# PatchPanel.net
KiCad netlist of a schematic drawn in EAGLE
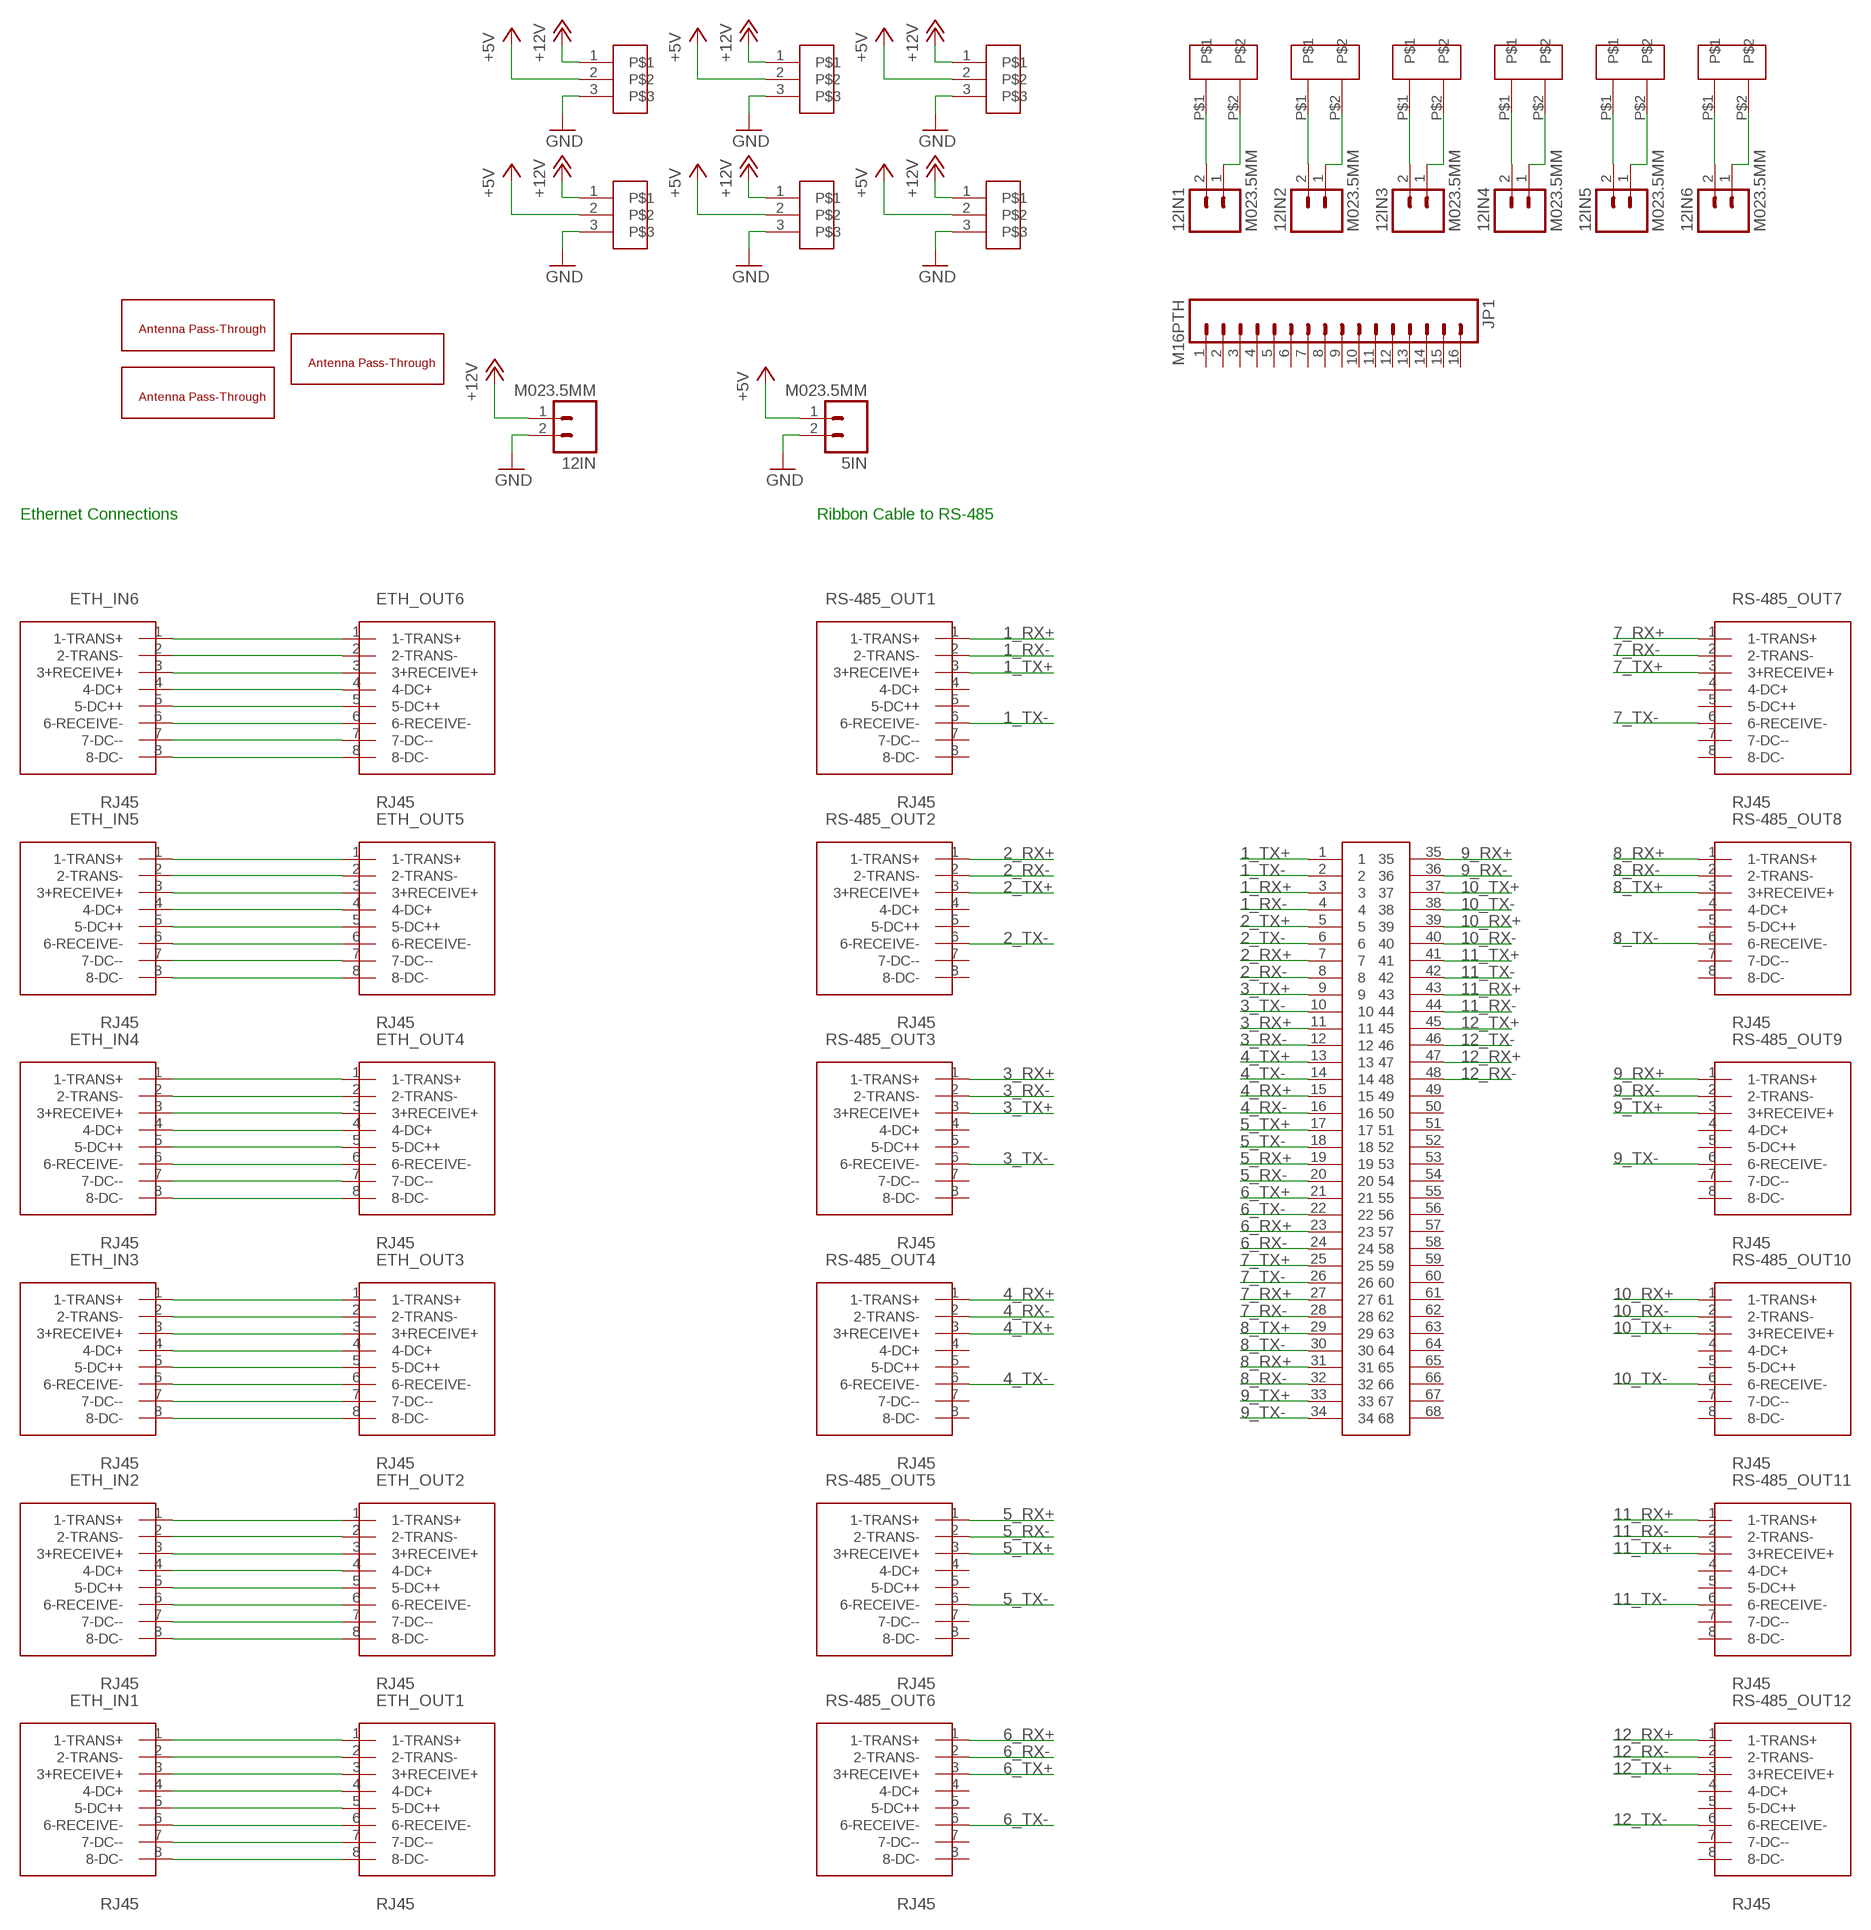
[diagram p0: schematic, sheet 1]

(export (version "E")
  (design (tool "Eeschema 10.0.6"))
  (components
    (comp (ref "5IN")
      (value "M023.5MM")
      (footprint "eagle-import:SCREWTERMINAL-3.5MM-2")
      (libsource (lib "eagle-import") (part "M023.5MM"))
    )
    (comp (ref "12IN")
      (value "M023.5MM")
      (footprint "eagle-import:SCREWTERMINAL-3.5MM-2")
      (libsource (lib "eagle-import") (part "M023.5MM"))
    )
    (comp (ref "12IN1")
      (value "M023.5MM")
      (footprint "eagle-import:SCREWTERMINAL-3.5MM-2")
      (libsource (lib "eagle-import") (part "M023.5MM"))
    )
    (comp (ref "12IN2")
      (value "M023.5MM")
      (footprint "eagle-import:SCREWTERMINAL-3.5MM-2")
      (libsource (lib "eagle-import") (part "M023.5MM"))
    )
    (comp (ref "12IN3")
      (value "M023.5MM")
      (footprint "eagle-import:SCREWTERMINAL-3.5MM-2")
      (libsource (lib "eagle-import") (part "M023.5MM"))
    )
    (comp (ref "12IN4")
      (value "M023.5MM")
      (footprint "eagle-import:SCREWTERMINAL-3.5MM-2")
      (libsource (lib "eagle-import") (part "M023.5MM"))
    )
    (comp (ref "12IN5")
      (value "M023.5MM")
      (footprint "eagle-import:SCREWTERMINAL-3.5MM-2")
      (libsource (lib "eagle-import") (part "M023.5MM"))
    )
    (comp (ref "12IN6")
      (value "M023.5MM")
      (footprint "eagle-import:SCREWTERMINAL-3.5MM-2")
      (libsource (lib "eagle-import") (part "M023.5MM"))
    )
    (comp (ref "ETH_IN1")
      (value "RJ45")
      (footprint "eagle-import:RJ45-CAT5E")
      (libsource (lib "eagle-import") (part "RJ45"))
    )
    (comp (ref "ETH_IN2")
      (value "RJ45")
      (footprint "eagle-import:RJ45-CAT5E")
      (libsource (lib "eagle-import") (part "RJ45"))
    )
    (comp (ref "ETH_IN3")
      (value "RJ45")
      (footprint "eagle-import:RJ45-CAT5E")
      (libsource (lib "eagle-import") (part "RJ45"))
    )
    (comp (ref "ETH_IN4")
      (value "RJ45")
      (footprint "eagle-import:RJ45-CAT5E")
      (libsource (lib "eagle-import") (part "RJ45"))
    )
    (comp (ref "ETH_IN5")
      (value "RJ45")
      (footprint "eagle-import:RJ45-CAT5E")
      (libsource (lib "eagle-import") (part "RJ45"))
    )
    (comp (ref "ETH_IN6")
      (value "RJ45")
      (footprint "eagle-import:RJ45-CAT5E")
      (libsource (lib "eagle-import") (part "RJ45"))
    )
    (comp (ref "ETH_OUT1")
      (value "RJ45")
      (footprint "eagle-import:RJ45-CAT5E")
      (libsource (lib "eagle-import") (part "RJ45"))
    )
    (comp (ref "ETH_OUT2")
      (value "RJ45")
      (footprint "eagle-import:RJ45-CAT5E")
      (libsource (lib "eagle-import") (part "RJ45"))
    )
    (comp (ref "ETH_OUT3")
      (value "RJ45")
      (footprint "eagle-import:RJ45-CAT5E")
      (libsource (lib "eagle-import") (part "RJ45"))
    )
    (comp (ref "ETH_OUT4")
      (value "RJ45")
      (footprint "eagle-import:RJ45-CAT5E")
      (libsource (lib "eagle-import") (part "RJ45"))
    )
    (comp (ref "ETH_OUT5")
      (value "RJ45")
      (footprint "eagle-import:RJ45-CAT5E")
      (libsource (lib "eagle-import") (part "RJ45"))
    )
    (comp (ref "ETH_OUT6")
      (value "RJ45")
      (footprint "eagle-import:RJ45-CAT5E")
      (libsource (lib "eagle-import") (part "RJ45"))
    )
    (comp (ref "JP1")
      (value "M16PTH")
      (footprint "eagle-import:1X16")
      (libsource (lib "eagle-import") (part "M16PTH"))
    )
    (comp (ref "RS-485_OUT1")
      (value "RJ45")
      (footprint "eagle-import:RJ45-CAT5E")
      (libsource (lib "eagle-import") (part "RJ45"))
    )
    (comp (ref "RS-485_OUT2")
      (value "RJ45")
      (footprint "eagle-import:RJ45-CAT5E")
      (libsource (lib "eagle-import") (part "RJ45"))
    )
    (comp (ref "RS-485_OUT3")
      (value "RJ45")
      (footprint "eagle-import:RJ45-CAT5E")
      (libsource (lib "eagle-import") (part "RJ45"))
    )
    (comp (ref "RS-485_OUT4")
      (value "RJ45")
      (footprint "eagle-import:RJ45-CAT5E")
      (libsource (lib "eagle-import") (part "RJ45"))
    )
    (comp (ref "RS-485_OUT5")
      (value "RJ45")
      (footprint "eagle-import:RJ45-CAT5E")
      (libsource (lib "eagle-import") (part "RJ45"))
    )
    (comp (ref "RS-485_OUT6")
      (value "RJ45")
      (footprint "eagle-import:RJ45-CAT5E")
      (libsource (lib "eagle-import") (part "RJ45"))
    )
    (comp (ref "RS-485_OUT7")
      (value "RJ45")
      (footprint "eagle-import:RJ45-CAT5E")
      (libsource (lib "eagle-import") (part "RJ45"))
    )
    (comp (ref "RS-485_OUT8")
      (value "RJ45")
      (footprint "eagle-import:RJ45-CAT5E")
      (libsource (lib "eagle-import") (part "RJ45"))
    )
    (comp (ref "RS-485_OUT9")
      (value "RJ45")
      (footprint "eagle-import:RJ45-CAT5E")
      (libsource (lib "eagle-import") (part "RJ45"))
    )
    (comp (ref "RS-485_OUT10")
      (value "RJ45")
      (footprint "eagle-import:RJ45-CAT5E")
      (libsource (lib "eagle-import") (part "RJ45"))
    )
    (comp (ref "RS-485_OUT11")
      (value "RJ45")
      (footprint "eagle-import:RJ45-CAT5E")
      (libsource (lib "eagle-import") (part "RJ45"))
    )
    (comp (ref "RS-485_OUT12")
      (value "RJ45")
      (footprint "eagle-import:RJ45-CAT5E")
      (libsource (lib "eagle-import") (part "RJ45"))
    )
    (comp (ref "U$1")
      (value "TB60050685100")
      (footprint "eagle-import:60050685100")
      (libsource (lib "eagle-import") (part "TB60050685100"))
    )
    (comp (ref "U$2")
      (value "3PIN")
      (footprint "eagle-import:0.93_")
      (libsource (lib "eagle-import") (part "3PIN"))
    )
    (comp (ref "U$3")
      (value "3PIN")
      (footprint "eagle-import:0.93_")
      (libsource (lib "eagle-import") (part "3PIN"))
    )
    (comp (ref "U$4")
      (value "3PIN")
      (footprint "eagle-import:0.93_")
      (libsource (lib "eagle-import") (part "3PIN"))
    )
    (comp (ref "U$5")
      (value "3PIN")
      (footprint "eagle-import:0.93_")
      (libsource (lib "eagle-import") (part "3PIN"))
    )
    (comp (ref "U$6")
      (value "3PIN")
      (footprint "eagle-import:0.93_")
      (libsource (lib "eagle-import") (part "3PIN"))
    )
    (comp (ref "U$7")
      (value "3PIN")
      (footprint "eagle-import:0.93_")
      (libsource (lib "eagle-import") (part "3PIN"))
    )
    (comp (ref "U$8")
      (value "MLX-2")
      (footprint "eagle-import:42002-2")
      (libsource (lib "eagle-import") (part "MLX-2"))
    )
    (comp (ref "U$9")
      (value "MLX-2")
      (footprint "eagle-import:42002-2")
      (libsource (lib "eagle-import") (part "MLX-2"))
    )
    (comp (ref "U$10")
      (value "MLX-2")
      (footprint "eagle-import:42002-2")
      (libsource (lib "eagle-import") (part "MLX-2"))
    )
    (comp (ref "U$11")
      (value "MLX-2")
      (footprint "eagle-import:42002-2")
      (libsource (lib "eagle-import") (part "MLX-2"))
    )
    (comp (ref "U$12")
      (value "MLX-2")
      (footprint "eagle-import:42002-2")
      (libsource (lib "eagle-import") (part "MLX-2"))
    )
    (comp (ref "U$13")
      (value "MLX-2")
      (footprint "eagle-import:42002-2")
      (libsource (lib "eagle-import") (part "MLX-2"))
    )
    (comp (ref "U$14")
      (value "N-TYPE-THRU")
      (footprint "eagle-import:N-TYPE")
      (libsource (lib "eagle-import") (part "N-TYPE-THRU"))
    )
    (comp (ref "U$15")
      (value "N-TYPE-THRU")
      (footprint "eagle-import:N-TYPE")
      (libsource (lib "eagle-import") (part "N-TYPE-THRU"))
    )
    (comp (ref "U$16")
      (value "SMA-THRU")
      (footprint "eagle-import:SMA")
      (libsource (lib "eagle-import") (part "SMA-THRU"))
    )
  )
  (nets
    (net (code "1") (name "+5V") (class "Default")
      (node (ref "5IN") (pin "1") (pinfunction "1_1") (pintype "passive"))
      (node (ref "U$2") (pin "2") (pinfunction "P$2_2") (pintype "bidirectional"))
      (node (ref "U$3") (pin "2") (pinfunction "P$2_2") (pintype "bidirectional"))
      (node (ref "U$4") (pin "2") (pinfunction "P$2_2") (pintype "bidirectional"))
      (node (ref "U$5") (pin "2") (pinfunction "P$2_2") (pintype "bidirectional"))
      (node (ref "U$6") (pin "2") (pinfunction "P$2_2") (pintype "bidirectional"))
      (node (ref "U$7") (pin "2") (pinfunction "P$2_2") (pintype "bidirectional"))
    )
    (net (code "2") (name "+12V") (class "Default")
      (node (ref "12IN") (pin "1") (pinfunction "1_1") (pintype "passive"))
      (node (ref "U$2") (pin "1") (pinfunction "P$1_1") (pintype "bidirectional"))
      (node (ref "U$3") (pin "1") (pinfunction "P$1_1") (pintype "bidirectional"))
      (node (ref "U$4") (pin "1") (pinfunction "P$1_1") (pintype "bidirectional"))
      (node (ref "U$5") (pin "1") (pinfunction "P$1_1") (pintype "bidirectional"))
      (node (ref "U$6") (pin "1") (pinfunction "P$1_1") (pintype "bidirectional"))
      (node (ref "U$7") (pin "1") (pinfunction "P$1_1") (pintype "bidirectional"))
    )
    (net (code "3") (name "/1_RX+") (class "Default")
      (node (ref "RS-485_OUT1") (pin "1") (pinfunction "1-TRANS+_1") (pintype "bidirectional"))
      (node (ref "U$1") (pin "3") (pinfunction "3_3") (pintype "bidirectional"))
    )
    (net (code "4") (name "/1_RX-") (class "Default")
      (node (ref "RS-485_OUT1") (pin "2") (pinfunction "2-TRANS-_2") (pintype "bidirectional"))
      (node (ref "U$1") (pin "4") (pinfunction "4_4") (pintype "bidirectional"))
    )
    (net (code "5") (name "/1_TX+") (class "Default")
      (node (ref "RS-485_OUT1") (pin "3") (pinfunction "3+RECEIVE+_3") (pintype "bidirectional"))
      (node (ref "U$1") (pin "1") (pinfunction "1_1") (pintype "bidirectional"))
    )
    (net (code "6") (name "/1_TX-") (class "Default")
      (node (ref "RS-485_OUT1") (pin "6") (pinfunction "6-RECEIVE-_6") (pintype "bidirectional"))
      (node (ref "U$1") (pin "2") (pinfunction "2_2") (pintype "bidirectional"))
    )
    (net (code "7") (name "/2_RX+") (class "Default")
      (node (ref "RS-485_OUT2") (pin "1") (pinfunction "1-TRANS+_1") (pintype "bidirectional"))
      (node (ref "U$1") (pin "7") (pinfunction "7_7") (pintype "bidirectional"))
    )
    (net (code "8") (name "/2_RX-") (class "Default")
      (node (ref "RS-485_OUT2") (pin "2") (pinfunction "2-TRANS-_2") (pintype "bidirectional"))
      (node (ref "U$1") (pin "8") (pinfunction "8_8") (pintype "bidirectional"))
    )
    (net (code "9") (name "/2_TX+") (class "Default")
      (node (ref "RS-485_OUT2") (pin "3") (pinfunction "3+RECEIVE+_3") (pintype "bidirectional"))
      (node (ref "U$1") (pin "5") (pinfunction "5_5") (pintype "bidirectional"))
    )
    (net (code "10") (name "/2_TX-") (class "Default")
      (node (ref "RS-485_OUT2") (pin "6") (pinfunction "6-RECEIVE-_6") (pintype "bidirectional"))
      (node (ref "U$1") (pin "6") (pinfunction "6_6") (pintype "bidirectional"))
    )
    (net (code "11") (name "/3_RX+") (class "Default")
      (node (ref "RS-485_OUT3") (pin "1") (pinfunction "1-TRANS+_1") (pintype "bidirectional"))
      (node (ref "U$1") (pin "11") (pinfunction "11_11") (pintype "bidirectional"))
    )
    (net (code "12") (name "/3_RX-") (class "Default")
      (node (ref "RS-485_OUT3") (pin "2") (pinfunction "2-TRANS-_2") (pintype "bidirectional"))
      (node (ref "U$1") (pin "12") (pinfunction "12_12") (pintype "bidirectional"))
    )
    (net (code "13") (name "/3_TX+") (class "Default")
      (node (ref "RS-485_OUT3") (pin "3") (pinfunction "3+RECEIVE+_3") (pintype "bidirectional"))
      (node (ref "U$1") (pin "9") (pinfunction "9_9") (pintype "bidirectional"))
    )
    (net (code "14") (name "/3_TX-") (class "Default")
      (node (ref "RS-485_OUT3") (pin "6") (pinfunction "6-RECEIVE-_6") (pintype "bidirectional"))
      (node (ref "U$1") (pin "10") (pinfunction "10_10") (pintype "bidirectional"))
    )
    (net (code "15") (name "/4_RX+") (class "Default")
      (node (ref "RS-485_OUT4") (pin "1") (pinfunction "1-TRANS+_1") (pintype "bidirectional"))
      (node (ref "U$1") (pin "15") (pinfunction "15_15") (pintype "bidirectional"))
    )
    (net (code "16") (name "/4_RX-") (class "Default")
      (node (ref "RS-485_OUT4") (pin "2") (pinfunction "2-TRANS-_2") (pintype "bidirectional"))
      (node (ref "U$1") (pin "16") (pinfunction "16_16") (pintype "bidirectional"))
    )
    (net (code "17") (name "/4_TX+") (class "Default")
      (node (ref "RS-485_OUT4") (pin "3") (pinfunction "3+RECEIVE+_3") (pintype "bidirectional"))
      (node (ref "U$1") (pin "13") (pinfunction "13_13") (pintype "bidirectional"))
    )
    (net (code "18") (name "/4_TX-") (class "Default")
      (node (ref "RS-485_OUT4") (pin "6") (pinfunction "6-RECEIVE-_6") (pintype "bidirectional"))
      (node (ref "U$1") (pin "14") (pinfunction "14_14") (pintype "bidirectional"))
    )
    (net (code "19") (name "/5_RX+") (class "Default")
      (node (ref "RS-485_OUT5") (pin "1") (pinfunction "1-TRANS+_1") (pintype "bidirectional"))
      (node (ref "U$1") (pin "19") (pinfunction "19_19") (pintype "bidirectional"))
    )
    (net (code "20") (name "/5_RX-") (class "Default")
      (node (ref "RS-485_OUT5") (pin "2") (pinfunction "2-TRANS-_2") (pintype "bidirectional"))
      (node (ref "U$1") (pin "20") (pinfunction "20_20") (pintype "bidirectional"))
    )
    (net (code "21") (name "/5_TX+") (class "Default")
      (node (ref "RS-485_OUT5") (pin "3") (pinfunction "3+RECEIVE+_3") (pintype "bidirectional"))
      (node (ref "U$1") (pin "17") (pinfunction "17_17") (pintype "bidirectional"))
    )
    (net (code "22") (name "/5_TX-") (class "Default")
      (node (ref "RS-485_OUT5") (pin "6") (pinfunction "6-RECEIVE-_6") (pintype "bidirectional"))
      (node (ref "U$1") (pin "18") (pinfunction "18_18") (pintype "bidirectional"))
    )
    (net (code "23") (name "/6_RX+") (class "Default")
      (node (ref "RS-485_OUT6") (pin "1") (pinfunction "1-TRANS+_1") (pintype "bidirectional"))
      (node (ref "U$1") (pin "23") (pinfunction "23_23") (pintype "bidirectional"))
    )
    (net (code "24") (name "/6_RX-") (class "Default")
      (node (ref "RS-485_OUT6") (pin "2") (pinfunction "2-TRANS-_2") (pintype "bidirectional"))
      (node (ref "U$1") (pin "24") (pinfunction "24_24") (pintype "bidirectional"))
    )
    (net (code "25") (name "/6_TX+") (class "Default")
      (node (ref "RS-485_OUT6") (pin "3") (pinfunction "3+RECEIVE+_3") (pintype "bidirectional"))
      (node (ref "U$1") (pin "21") (pinfunction "21_21") (pintype "bidirectional"))
    )
    (net (code "26") (name "/6_TX-") (class "Default")
      (node (ref "RS-485_OUT6") (pin "6") (pinfunction "6-RECEIVE-_6") (pintype "bidirectional"))
      (node (ref "U$1") (pin "22") (pinfunction "22_22") (pintype "bidirectional"))
    )
    (net (code "27") (name "/7_RX+") (class "Default")
      (node (ref "RS-485_OUT7") (pin "1") (pinfunction "1-TRANS+_1") (pintype "bidirectional"))
      (node (ref "U$1") (pin "27") (pinfunction "27_27") (pintype "bidirectional"))
    )
    (net (code "28") (name "/7_RX-") (class "Default")
      (node (ref "RS-485_OUT7") (pin "2") (pinfunction "2-TRANS-_2") (pintype "bidirectional"))
      (node (ref "U$1") (pin "28") (pinfunction "28_28") (pintype "bidirectional"))
    )
    (net (code "29") (name "/7_TX+") (class "Default")
      (node (ref "RS-485_OUT7") (pin "3") (pinfunction "3+RECEIVE+_3") (pintype "bidirectional"))
      (node (ref "U$1") (pin "25") (pinfunction "25_25") (pintype "bidirectional"))
    )
    (net (code "30") (name "/7_TX-") (class "Default")
      (node (ref "RS-485_OUT7") (pin "6") (pinfunction "6-RECEIVE-_6") (pintype "bidirectional"))
      (node (ref "U$1") (pin "26") (pinfunction "26_26") (pintype "bidirectional"))
    )
    (net (code "31") (name "/8_RX+") (class "Default")
      (node (ref "RS-485_OUT8") (pin "1") (pinfunction "1-TRANS+_1") (pintype "bidirectional"))
      (node (ref "U$1") (pin "31") (pinfunction "31_31") (pintype "bidirectional"))
    )
    (net (code "32") (name "/8_RX-") (class "Default")
      (node (ref "RS-485_OUT8") (pin "2") (pinfunction "2-TRANS-_2") (pintype "bidirectional"))
      (node (ref "U$1") (pin "32") (pinfunction "32_32") (pintype "bidirectional"))
    )
    (net (code "33") (name "/8_TX+") (class "Default")
      (node (ref "RS-485_OUT8") (pin "3") (pinfunction "3+RECEIVE+_3") (pintype "bidirectional"))
      (node (ref "U$1") (pin "29") (pinfunction "29_29") (pintype "bidirectional"))
    )
    (net (code "34") (name "/8_TX-") (class "Default")
      (node (ref "RS-485_OUT8") (pin "6") (pinfunction "6-RECEIVE-_6") (pintype "bidirectional"))
      (node (ref "U$1") (pin "30") (pinfunction "30_30") (pintype "bidirectional"))
    )
    (net (code "35") (name "/9_RX+") (class "Default")
      (node (ref "RS-485_OUT9") (pin "1") (pinfunction "1-TRANS+_1") (pintype "bidirectional"))
      (node (ref "U$1") (pin "35") (pinfunction "35_35") (pintype "bidirectional"))
    )
    (net (code "36") (name "/9_RX-") (class "Default")
      (node (ref "RS-485_OUT9") (pin "2") (pinfunction "2-TRANS-_2") (pintype "bidirectional"))
      (node (ref "U$1") (pin "36") (pinfunction "36_36") (pintype "bidirectional"))
    )
    (net (code "37") (name "/9_TX+") (class "Default")
      (node (ref "RS-485_OUT9") (pin "3") (pinfunction "3+RECEIVE+_3") (pintype "bidirectional"))
      (node (ref "U$1") (pin "33") (pinfunction "33_33") (pintype "bidirectional"))
    )
    (net (code "38") (name "/9_TX-") (class "Default")
      (node (ref "RS-485_OUT9") (pin "6") (pinfunction "6-RECEIVE-_6") (pintype "bidirectional"))
      (node (ref "U$1") (pin "34") (pinfunction "34_34") (pintype "bidirectional"))
    )
    (net (code "39") (name "/10_RX+") (class "Default")
      (node (ref "RS-485_OUT10") (pin "1") (pinfunction "1-TRANS+_1") (pintype "bidirectional"))
      (node (ref "U$1") (pin "39") (pinfunction "39_39") (pintype "bidirectional"))
    )
    (net (code "40") (name "/10_RX-") (class "Default")
      (node (ref "RS-485_OUT10") (pin "2") (pinfunction "2-TRANS-_2") (pintype "bidirectional"))
      (node (ref "U$1") (pin "40") (pinfunction "40_40") (pintype "bidirectional"))
    )
    (net (code "41") (name "/10_TX+") (class "Default")
      (node (ref "RS-485_OUT10") (pin "3") (pinfunction "3+RECEIVE+_3") (pintype "bidirectional"))
      (node (ref "U$1") (pin "37") (pinfunction "37_37") (pintype "bidirectional"))
    )
    (net (code "42") (name "/10_TX-") (class "Default")
      (node (ref "RS-485_OUT10") (pin "6") (pinfunction "6-RECEIVE-_6") (pintype "bidirectional"))
      (node (ref "U$1") (pin "38") (pinfunction "38_38") (pintype "bidirectional"))
    )
    (net (code "43") (name "/11_RX+") (class "Default")
      (node (ref "RS-485_OUT11") (pin "1") (pinfunction "1-TRANS+_1") (pintype "bidirectional"))
      (node (ref "U$1") (pin "43") (pinfunction "43_43") (pintype "bidirectional"))
    )
    (net (code "44") (name "/11_RX-") (class "Default")
      (node (ref "RS-485_OUT11") (pin "2") (pinfunction "2-TRANS-_2") (pintype "bidirectional"))
      (node (ref "U$1") (pin "44") (pinfunction "44_44") (pintype "bidirectional"))
    )
    (net (code "45") (name "/11_TX+") (class "Default")
      (node (ref "RS-485_OUT11") (pin "3") (pinfunction "3+RECEIVE+_3") (pintype "bidirectional"))
      (node (ref "U$1") (pin "41") (pinfunction "41_41") (pintype "bidirectional"))
    )
    (net (code "46") (name "/11_TX-") (class "Default")
      (node (ref "RS-485_OUT11") (pin "6") (pinfunction "6-RECEIVE-_6") (pintype "bidirectional"))
      (node (ref "U$1") (pin "42") (pinfunction "42_42") (pintype "bidirectional"))
    )
    (net (code "47") (name "/12_RX+") (class "Default")
      (node (ref "RS-485_OUT12") (pin "1") (pinfunction "1-TRANS+_1") (pintype "bidirectional"))
      (node (ref "U$1") (pin "47") (pinfunction "47_47") (pintype "bidirectional"))
    )
    (net (code "48") (name "/12_RX-") (class "Default")
      (node (ref "RS-485_OUT12") (pin "2") (pinfunction "2-TRANS-_2") (pintype "bidirectional"))
      (node (ref "U$1") (pin "48") (pinfunction "48_48") (pintype "bidirectional"))
    )
    (net (code "49") (name "/12_TX+") (class "Default")
      (node (ref "RS-485_OUT12") (pin "3") (pinfunction "3+RECEIVE+_3") (pintype "bidirectional"))
      (node (ref "U$1") (pin "45") (pinfunction "45_45") (pintype "bidirectional"))
    )
    (net (code "50") (name "/12_TX-") (class "Default")
      (node (ref "RS-485_OUT12") (pin "6") (pinfunction "6-RECEIVE-_6") (pintype "bidirectional"))
      (node (ref "U$1") (pin "46") (pinfunction "46_46") (pintype "bidirectional"))
    )
    (net (code "51") (name "GND") (class "Default")
      (node (ref "12IN") (pin "2") (pinfunction "2_2") (pintype "passive"))
      (node (ref "5IN") (pin "2") (pinfunction "2_2") (pintype "passive"))
      (node (ref "U$2") (pin "3") (pinfunction "P$3_3") (pintype "bidirectional"))
      (node (ref "U$3") (pin "3") (pinfunction "P$3_3") (pintype "bidirectional"))
      (node (ref "U$4") (pin "3") (pinfunction "P$3_3") (pintype "bidirectional"))
      (node (ref "U$5") (pin "3") (pinfunction "P$3_3") (pintype "bidirectional"))
      (node (ref "U$6") (pin "3") (pinfunction "P$3_3") (pintype "bidirectional"))
      (node (ref "U$7") (pin "3") (pinfunction "P$3_3") (pintype "bidirectional"))
    )
    (net (code "52") (name "Net-(12IN1-Pad1)") (class "Default")
      (node (ref "12IN1") (pin "1") (pinfunction "1_1") (pintype "passive"))
      (node (ref "U$8") (pin "P$2") (pinfunction "P$2_P$2") (pintype "bidirectional"))
    )
    (net (code "53") (name "Net-(12IN1-Pad2)") (class "Default")
      (node (ref "12IN1") (pin "2") (pinfunction "2_2") (pintype "passive"))
      (node (ref "U$8") (pin "P$1") (pinfunction "P$1_P$1") (pintype "bidirectional"))
    )
    (net (code "54") (name "Net-(12IN2-Pad1)") (class "Default")
      (node (ref "12IN2") (pin "1") (pinfunction "1_1") (pintype "passive"))
      (node (ref "U$9") (pin "P$2") (pinfunction "P$2_P$2") (pintype "bidirectional"))
    )
    (net (code "55") (name "Net-(12IN2-Pad2)") (class "Default")
      (node (ref "12IN2") (pin "2") (pinfunction "2_2") (pintype "passive"))
      (node (ref "U$9") (pin "P$1") (pinfunction "P$1_P$1") (pintype "bidirectional"))
    )
    (net (code "56") (name "Net-(12IN3-Pad1)") (class "Default")
      (node (ref "12IN3") (pin "1") (pinfunction "1_1") (pintype "passive"))
      (node (ref "U$10") (pin "P$2") (pinfunction "P$2_P$2") (pintype "bidirectional"))
    )
    (net (code "57") (name "Net-(12IN3-Pad2)") (class "Default")
      (node (ref "12IN3") (pin "2") (pinfunction "2_2") (pintype "passive"))
      (node (ref "U$10") (pin "P$1") (pinfunction "P$1_P$1") (pintype "bidirectional"))
    )
    (net (code "58") (name "Net-(12IN4-Pad1)") (class "Default")
      (node (ref "12IN4") (pin "1") (pinfunction "1_1") (pintype "passive"))
      (node (ref "U$11") (pin "P$2") (pinfunction "P$2_P$2") (pintype "bidirectional"))
    )
    (net (code "59") (name "Net-(12IN4-Pad2)") (class "Default")
      (node (ref "12IN4") (pin "2") (pinfunction "2_2") (pintype "passive"))
      (node (ref "U$11") (pin "P$1") (pinfunction "P$1_P$1") (pintype "bidirectional"))
    )
    (net (code "60") (name "Net-(12IN5-Pad1)") (class "Default")
      (node (ref "12IN5") (pin "1") (pinfunction "1_1") (pintype "passive"))
      (node (ref "U$12") (pin "P$2") (pinfunction "P$2_P$2") (pintype "bidirectional"))
    )
    (net (code "61") (name "Net-(12IN5-Pad2)") (class "Default")
      (node (ref "12IN5") (pin "2") (pinfunction "2_2") (pintype "passive"))
      (node (ref "U$12") (pin "P$1") (pinfunction "P$1_P$1") (pintype "bidirectional"))
    )
    (net (code "62") (name "Net-(12IN6-Pad1)") (class "Default")
      (node (ref "12IN6") (pin "1") (pinfunction "1_1") (pintype "passive"))
      (node (ref "U$13") (pin "P$2") (pinfunction "P$2_P$2") (pintype "bidirectional"))
    )
    (net (code "63") (name "Net-(12IN6-Pad2)") (class "Default")
      (node (ref "12IN6") (pin "2") (pinfunction "2_2") (pintype "passive"))
      (node (ref "U$13") (pin "P$1") (pinfunction "P$1_P$1") (pintype "bidirectional"))
    )
    (net (code "64") (name "Net-(ETH_IN1-1-TRANS+)") (class "Default")
      (node (ref "ETH_IN1") (pin "1") (pinfunction "1-TRANS+_1") (pintype "bidirectional"))
      (node (ref "ETH_OUT1") (pin "1") (pinfunction "1-TRANS+_1") (pintype "bidirectional"))
    )
    (net (code "65") (name "Net-(ETH_IN1-2-TRANS-)") (class "Default")
      (node (ref "ETH_IN1") (pin "2") (pinfunction "2-TRANS-_2") (pintype "bidirectional"))
      (node (ref "ETH_OUT1") (pin "2") (pinfunction "2-TRANS-_2") (pintype "bidirectional"))
    )
    (net (code "66") (name "Net-(ETH_IN1-3+RECEIVE+)") (class "Default")
      (node (ref "ETH_IN1") (pin "3") (pinfunction "3+RECEIVE+_3") (pintype "bidirectional"))
      (node (ref "ETH_OUT1") (pin "3") (pinfunction "3+RECEIVE+_3") (pintype "bidirectional"))
    )
    (net (code "67") (name "Net-(ETH_IN1-4-DC+)") (class "Default")
      (node (ref "ETH_IN1") (pin "4") (pinfunction "4-DC+_4") (pintype "bidirectional"))
      (node (ref "ETH_OUT1") (pin "4") (pinfunction "4-DC+_4") (pintype "bidirectional"))
    )
    (net (code "68") (name "Net-(ETH_IN1-5-DC++)") (class "Default")
      (node (ref "ETH_IN1") (pin "5") (pinfunction "5-DC++_5") (pintype "bidirectional"))
      (node (ref "ETH_OUT1") (pin "5") (pinfunction "5-DC++_5") (pintype "bidirectional"))
    )
    (net (code "69") (name "Net-(ETH_IN1-6-RECEIVE-)") (class "Default")
      (node (ref "ETH_IN1") (pin "6") (pinfunction "6-RECEIVE-_6") (pintype "bidirectional"))
      (node (ref "ETH_OUT1") (pin "6") (pinfunction "6-RECEIVE-_6") (pintype "bidirectional"))
    )
    (net (code "70") (name "Net-(ETH_IN1-7-DC--)") (class "Default")
      (node (ref "ETH_IN1") (pin "7") (pinfunction "7-DC--_7") (pintype "bidirectional"))
      (node (ref "ETH_OUT1") (pin "7") (pinfunction "7-DC--_7") (pintype "bidirectional"))
    )
    (net (code "71") (name "Net-(ETH_IN1-8-DC-)") (class "Default")
      (node (ref "ETH_IN1") (pin "8") (pinfunction "8-DC-_8") (pintype "bidirectional"))
      (node (ref "ETH_OUT1") (pin "8") (pinfunction "8-DC-_8") (pintype "bidirectional"))
    )
    (net (code "72") (name "Net-(ETH_IN2-1-TRANS+)") (class "Default")
      (node (ref "ETH_IN2") (pin "1") (pinfunction "1-TRANS+_1") (pintype "bidirectional"))
      (node (ref "ETH_OUT2") (pin "1") (pinfunction "1-TRANS+_1") (pintype "bidirectional"))
    )
    (net (code "73") (name "Net-(ETH_IN2-2-TRANS-)") (class "Default")
      (node (ref "ETH_IN2") (pin "2") (pinfunction "2-TRANS-_2") (pintype "bidirectional"))
      (node (ref "ETH_OUT2") (pin "2") (pinfunction "2-TRANS-_2") (pintype "bidirectional"))
    )
    (net (code "74") (name "Net-(ETH_IN2-3+RECEIVE+)") (class "Default")
      (node (ref "ETH_IN2") (pin "3") (pinfunction "3+RECEIVE+_3") (pintype "bidirectional"))
      (node (ref "ETH_OUT2") (pin "3") (pinfunction "3+RECEIVE+_3") (pintype "bidirectional"))
    )
    (net (code "75") (name "Net-(ETH_IN2-4-DC+)") (class "Default")
      (node (ref "ETH_IN2") (pin "4") (pinfunction "4-DC+_4") (pintype "bidirectional"))
      (node (ref "ETH_OUT2") (pin "4") (pinfunction "4-DC+_4") (pintype "bidirectional"))
    )
    (net (code "76") (name "Net-(ETH_IN2-5-DC++)") (class "Default")
      (node (ref "ETH_IN2") (pin "5") (pinfunction "5-DC++_5") (pintype "bidirectional"))
      (node (ref "ETH_OUT2") (pin "5") (pinfunction "5-DC++_5") (pintype "bidirectional"))
    )
    (net (code "77") (name "Net-(ETH_IN2-6-RECEIVE-)") (class "Default")
      (node (ref "ETH_IN2") (pin "6") (pinfunction "6-RECEIVE-_6") (pintype "bidirectional"))
      (node (ref "ETH_OUT2") (pin "6") (pinfunction "6-RECEIVE-_6") (pintype "bidirectional"))
    )
    (net (code "78") (name "Net-(ETH_IN2-7-DC--)") (class "Default")
      (node (ref "ETH_IN2") (pin "7") (pinfunction "7-DC--_7") (pintype "bidirectional"))
      (node (ref "ETH_OUT2") (pin "7") (pinfunction "7-DC--_7") (pintype "bidirectional"))
    )
    (net (code "79") (name "Net-(ETH_IN2-8-DC-)") (class "Default")
      (node (ref "ETH_IN2") (pin "8") (pinfunction "8-DC-_8") (pintype "bidirectional"))
      (node (ref "ETH_OUT2") (pin "8") (pinfunction "8-DC-_8") (pintype "bidirectional"))
    )
    (net (code "80") (name "Net-(ETH_IN3-1-TRANS+)") (class "Default")
      (node (ref "ETH_IN3") (pin "1") (pinfunction "1-TRANS+_1") (pintype "bidirectional"))
      (node (ref "ETH_OUT3") (pin "1") (pinfunction "1-TRANS+_1") (pintype "bidirectional"))
    )
    (net (code "81") (name "Net-(ETH_IN3-2-TRANS-)") (class "Default")
      (node (ref "ETH_IN3") (pin "2") (pinfunction "2-TRANS-_2") (pintype "bidirectional"))
      (node (ref "ETH_OUT3") (pin "2") (pinfunction "2-TRANS-_2") (pintype "bidirectional"))
    )
    (net (code "82") (name "Net-(ETH_IN3-3+RECEIVE+)") (class "Default")
      (node (ref "ETH_IN3") (pin "3") (pinfunction "3+RECEIVE+_3") (pintype "bidirectional"))
      (node (ref "ETH_OUT3") (pin "3") (pinfunction "3+RECEIVE+_3") (pintype "bidirectional"))
    )
    (net (code "83") (name "Net-(ETH_IN3-4-DC+)") (class "Default")
      (node (ref "ETH_IN3") (pin "4") (pinfunction "4-DC+_4") (pintype "bidirectional"))
      (node (ref "ETH_OUT3") (pin "4") (pinfunction "4-DC+_4") (pintype "bidirectional"))
    )
    (net (code "84") (name "Net-(ETH_IN3-5-DC++)") (class "Default")
      (node (ref "ETH_IN3") (pin "5") (pinfunction "5-DC++_5") (pintype "bidirectional"))
      (node (ref "ETH_OUT3") (pin "5") (pinfunction "5-DC++_5") (pintype "bidirectional"))
    )
    (net (code "85") (name "Net-(ETH_IN3-6-RECEIVE-)") (class "Default")
      (node (ref "ETH_IN3") (pin "6") (pinfunction "6-RECEIVE-_6") (pintype "bidirectional"))
      (node (ref "ETH_OUT3") (pin "6") (pinfunction "6-RECEIVE-_6") (pintype "bidirectional"))
    )
    (net (code "86") (name "Net-(ETH_IN3-7-DC--)") (class "Default")
      (node (ref "ETH_IN3") (pin "7") (pinfunction "7-DC--_7") (pintype "bidirectional"))
      (node (ref "ETH_OUT3") (pin "7") (pinfunction "7-DC--_7") (pintype "bidirectional"))
    )
    (net (code "87") (name "Net-(ETH_IN3-8-DC-)") (class "Default")
      (node (ref "ETH_IN3") (pin "8") (pinfunction "8-DC-_8") (pintype "bidirectional"))
      (node (ref "ETH_OUT3") (pin "8") (pinfunction "8-DC-_8") (pintype "bidirectional"))
    )
    (net (code "88") (name "Net-(ETH_IN4-1-TRANS+)") (class "Default")
      (node (ref "ETH_IN4") (pin "1") (pinfunction "1-TRANS+_1") (pintype "bidirectional"))
      (node (ref "ETH_OUT4") (pin "1") (pinfunction "1-TRANS+_1") (pintype "bidirectional"))
    )
    (net (code "89") (name "Net-(ETH_IN4-2-TRANS-)") (class "Default")
      (node (ref "ETH_IN4") (pin "2") (pinfunction "2-TRANS-_2") (pintype "bidirectional"))
      (node (ref "ETH_OUT4") (pin "2") (pinfunction "2-TRANS-_2") (pintype "bidirectional"))
    )
    (net (code "90") (name "Net-(ETH_IN4-3+RECEIVE+)") (class "Default")
      (node (ref "ETH_IN4") (pin "3") (pinfunction "3+RECEIVE+_3") (pintype "bidirectional"))
      (node (ref "ETH_OUT4") (pin "3") (pinfunction "3+RECEIVE+_3") (pintype "bidirectional"))
    )
    (net (code "91") (name "Net-(ETH_IN4-4-DC+)") (class "Default")
      (node (ref "ETH_IN4") (pin "4") (pinfunction "4-DC+_4") (pintype "bidirectional"))
      (node (ref "ETH_OUT4") (pin "4") (pinfunction "4-DC+_4") (pintype "bidirectional"))
    )
    (net (code "92") (name "Net-(ETH_IN4-5-DC++)") (class "Default")
      (node (ref "ETH_IN4") (pin "5") (pinfunction "5-DC++_5") (pintype "bidirectional"))
      (node (ref "ETH_OUT4") (pin "5") (pinfunction "5-DC++_5") (pintype "bidirectional"))
    )
    (net (code "93") (name "Net-(ETH_IN4-6-RECEIVE-)") (class "Default")
      (node (ref "ETH_IN4") (pin "6") (pinfunction "6-RECEIVE-_6") (pintype "bidirectional"))
      (node (ref "ETH_OUT4") (pin "6") (pinfunction "6-RECEIVE-_6") (pintype "bidirectional"))
    )
    (net (code "94") (name "Net-(ETH_IN4-7-DC--)") (class "Default")
      (node (ref "ETH_IN4") (pin "7") (pinfunction "7-DC--_7") (pintype "bidirectional"))
      (node (ref "ETH_OUT4") (pin "7") (pinfunction "7-DC--_7") (pintype "bidirectional"))
    )
    (net (code "95") (name "Net-(ETH_IN4-8-DC-)") (class "Default")
      (node (ref "ETH_IN4") (pin "8") (pinfunction "8-DC-_8") (pintype "bidirectional"))
      (node (ref "ETH_OUT4") (pin "8") (pinfunction "8-DC-_8") (pintype "bidirectional"))
    )
    (net (code "96") (name "Net-(ETH_IN5-1-TRANS+)") (class "Default")
      (node (ref "ETH_IN5") (pin "1") (pinfunction "1-TRANS+_1") (pintype "bidirectional"))
      (node (ref "ETH_OUT5") (pin "1") (pinfunction "1-TRANS+_1") (pintype "bidirectional"))
    )
    (net (code "97") (name "Net-(ETH_IN5-2-TRANS-)") (class "Default")
      (node (ref "ETH_IN5") (pin "2") (pinfunction "2-TRANS-_2") (pintype "bidirectional"))
      (node (ref "ETH_OUT5") (pin "2") (pinfunction "2-TRANS-_2") (pintype "bidirectional"))
    )
    (net (code "98") (name "Net-(ETH_IN5-3+RECEIVE+)") (class "Default")
      (node (ref "ETH_IN5") (pin "3") (pinfunction "3+RECEIVE+_3") (pintype "bidirectional"))
      (node (ref "ETH_OUT5") (pin "3") (pinfunction "3+RECEIVE+_3") (pintype "bidirectional"))
    )
    (net (code "99") (name "Net-(ETH_IN5-4-DC+)") (class "Default")
      (node (ref "ETH_IN5") (pin "4") (pinfunction "4-DC+_4") (pintype "bidirectional"))
      (node (ref "ETH_OUT5") (pin "4") (pinfunction "4-DC+_4") (pintype "bidirectional"))
    )
    (net (code "100") (name "Net-(ETH_IN5-5-DC++)") (class "Default")
      (node (ref "ETH_IN5") (pin "5") (pinfunction "5-DC++_5") (pintype "bidirectional"))
      (node (ref "ETH_OUT5") (pin "5") (pinfunction "5-DC++_5") (pintype "bidirectional"))
    )
    (net (code "101") (name "Net-(ETH_IN5-6-RECEIVE-)") (class "Default")
      (node (ref "ETH_IN5") (pin "6") (pinfunction "6-RECEIVE-_6") (pintype "bidirectional"))
      (node (ref "ETH_OUT5") (pin "6") (pinfunction "6-RECEIVE-_6") (pintype "bidirectional"))
    )
    (net (code "102") (name "Net-(ETH_IN5-7-DC--)") (class "Default")
      (node (ref "ETH_IN5") (pin "7") (pinfunction "7-DC--_7") (pintype "bidirectional"))
      (node (ref "ETH_OUT5") (pin "7") (pinfunction "7-DC--_7") (pintype "bidirectional"))
    )
    (net (code "103") (name "Net-(ETH_IN5-8-DC-)") (class "Default")
      (node (ref "ETH_IN5") (pin "8") (pinfunction "8-DC-_8") (pintype "bidirectional"))
      (node (ref "ETH_OUT5") (pin "8") (pinfunction "8-DC-_8") (pintype "bidirectional"))
    )
    (net (code "104") (name "Net-(ETH_IN6-1-TRANS+)") (class "Default")
      (node (ref "ETH_IN6") (pin "1") (pinfunction "1-TRANS+_1") (pintype "bidirectional"))
      (node (ref "ETH_OUT6") (pin "1") (pinfunction "1-TRANS+_1") (pintype "bidirectional"))
    )
    (net (code "105") (name "Net-(ETH_IN6-2-TRANS-)") (class "Default")
      (node (ref "ETH_IN6") (pin "2") (pinfunction "2-TRANS-_2") (pintype "bidirectional"))
      (node (ref "ETH_OUT6") (pin "2") (pinfunction "2-TRANS-_2") (pintype "bidirectional"))
    )
    (net (code "106") (name "Net-(ETH_IN6-3+RECEIVE+)") (class "Default")
      (node (ref "ETH_IN6") (pin "3") (pinfunction "3+RECEIVE+_3") (pintype "bidirectional"))
      (node (ref "ETH_OUT6") (pin "3") (pinfunction "3+RECEIVE+_3") (pintype "bidirectional"))
    )
    (net (code "107") (name "Net-(ETH_IN6-4-DC+)") (class "Default")
      (node (ref "ETH_IN6") (pin "4") (pinfunction "4-DC+_4") (pintype "bidirectional"))
      (node (ref "ETH_OUT6") (pin "4") (pinfunction "4-DC+_4") (pintype "bidirectional"))
    )
    (net (code "108") (name "Net-(ETH_IN6-5-DC++)") (class "Default")
      (node (ref "ETH_IN6") (pin "5") (pinfunction "5-DC++_5") (pintype "bidirectional"))
      (node (ref "ETH_OUT6") (pin "5") (pinfunction "5-DC++_5") (pintype "bidirectional"))
    )
    (net (code "109") (name "Net-(ETH_IN6-6-RECEIVE-)") (class "Default")
      (node (ref "ETH_IN6") (pin "6") (pinfunction "6-RECEIVE-_6") (pintype "bidirectional"))
      (node (ref "ETH_OUT6") (pin "6") (pinfunction "6-RECEIVE-_6") (pintype "bidirectional"))
    )
    (net (code "110") (name "Net-(ETH_IN6-7-DC--)") (class "Default")
      (node (ref "ETH_IN6") (pin "7") (pinfunction "7-DC--_7") (pintype "bidirectional"))
      (node (ref "ETH_OUT6") (pin "7") (pinfunction "7-DC--_7") (pintype "bidirectional"))
    )
    (net (code "111") (name "Net-(ETH_IN6-8-DC-)") (class "Default")
      (node (ref "ETH_IN6") (pin "8") (pinfunction "8-DC-_8") (pintype "bidirectional"))
      (node (ref "ETH_OUT6") (pin "8") (pinfunction "8-DC-_8") (pintype "bidirectional"))
    )
    (net (code "112") (name "unconnected-(JP1-Pad1)") (class "Default")
      (node (ref "JP1") (pin "1") (pinfunction "1_1") (pintype "passive"))
    )
    (net (code "113") (name "unconnected-(JP1-Pad2)") (class "Default")
      (node (ref "JP1") (pin "2") (pinfunction "2_2") (pintype "passive"))
    )
    (net (code "114") (name "unconnected-(JP1-Pad3)") (class "Default")
      (node (ref "JP1") (pin "3") (pinfunction "3_3") (pintype "passive"))
    )
    (net (code "115") (name "unconnected-(JP1-Pad4)") (class "Default")
      (node (ref "JP1") (pin "4") (pinfunction "4_4") (pintype "passive"))
    )
    (net (code "116") (name "unconnected-(JP1-Pad5)") (class "Default")
      (node (ref "JP1") (pin "5") (pinfunction "5_5") (pintype "passive"))
    )
    (net (code "117") (name "unconnected-(JP1-Pad6)") (class "Default")
      (node (ref "JP1") (pin "6") (pinfunction "6_6") (pintype "passive"))
    )
    (net (code "118") (name "unconnected-(JP1-Pad7)") (class "Default")
      (node (ref "JP1") (pin "7") (pinfunction "7_7") (pintype "passive"))
    )
    (net (code "119") (name "unconnected-(JP1-Pad8)") (class "Default")
      (node (ref "JP1") (pin "8") (pinfunction "8_8") (pintype "passive"))
    )
    (net (code "120") (name "unconnected-(JP1-Pad9)") (class "Default")
      (node (ref "JP1") (pin "9") (pinfunction "9_9") (pintype "passive"))
    )
    (net (code "121") (name "unconnected-(JP1-Pad10)") (class "Default")
      (node (ref "JP1") (pin "10") (pinfunction "10_10") (pintype "passive"))
    )
    (net (code "122") (name "unconnected-(JP1-Pad11)") (class "Default")
      (node (ref "JP1") (pin "11") (pinfunction "11_11") (pintype "passive"))
    )
    (net (code "123") (name "unconnected-(JP1-Pad12)") (class "Default")
      (node (ref "JP1") (pin "12") (pinfunction "12_12") (pintype "passive"))
    )
    (net (code "124") (name "unconnected-(JP1-Pad13)") (class "Default")
      (node (ref "JP1") (pin "13") (pinfunction "13_13") (pintype "passive"))
    )
    (net (code "125") (name "unconnected-(JP1-Pad14)") (class "Default")
      (node (ref "JP1") (pin "14") (pinfunction "14_14") (pintype "passive"))
    )
    (net (code "126") (name "unconnected-(JP1-Pad15)") (class "Default")
      (node (ref "JP1") (pin "15") (pinfunction "15_15") (pintype "passive"))
    )
    (net (code "127") (name "unconnected-(JP1-Pad16)") (class "Default")
      (node (ref "JP1") (pin "16") (pinfunction "16_16") (pintype "passive"))
    )
    (net (code "128") (name "unconnected-(RS-485_OUT1-4-DC+-Pad4)") (class "Default")
      (node (ref "RS-485_OUT1") (pin "4") (pinfunction "4-DC+_4") (pintype "bidirectional"))
    )
    (net (code "129") (name "unconnected-(RS-485_OUT1-5-DC++-Pad5)") (class "Default")
      (node (ref "RS-485_OUT1") (pin "5") (pinfunction "5-DC++_5") (pintype "bidirectional"))
    )
    (net (code "130") (name "unconnected-(RS-485_OUT1-7-DC---Pad7)") (class "Default")
      (node (ref "RS-485_OUT1") (pin "7") (pinfunction "7-DC--_7") (pintype "bidirectional"))
    )
    (net (code "131") (name "unconnected-(RS-485_OUT1-8-DC--Pad8)") (class "Default")
      (node (ref "RS-485_OUT1") (pin "8") (pinfunction "8-DC-_8") (pintype "bidirectional"))
    )
    (net (code "132") (name "unconnected-(RS-485_OUT2-4-DC+-Pad4)") (class "Default")
      (node (ref "RS-485_OUT2") (pin "4") (pinfunction "4-DC+_4") (pintype "bidirectional"))
    )
    (net (code "133") (name "unconnected-(RS-485_OUT2-5-DC++-Pad5)") (class "Default")
      (node (ref "RS-485_OUT2") (pin "5") (pinfunction "5-DC++_5") (pintype "bidirectional"))
    )
    (net (code "134") (name "unconnected-(RS-485_OUT2-7-DC---Pad7)") (class "Default")
      (node (ref "RS-485_OUT2") (pin "7") (pinfunction "7-DC--_7") (pintype "bidirectional"))
    )
    (net (code "135") (name "unconnected-(RS-485_OUT2-8-DC--Pad8)") (class "Default")
      (node (ref "RS-485_OUT2") (pin "8") (pinfunction "8-DC-_8") (pintype "bidirectional"))
    )
    (net (code "136") (name "unconnected-(RS-485_OUT3-4-DC+-Pad4)") (class "Default")
      (node (ref "RS-485_OUT3") (pin "4") (pinfunction "4-DC+_4") (pintype "bidirectional"))
    )
    (net (code "137") (name "unconnected-(RS-485_OUT3-5-DC++-Pad5)") (class "Default")
      (node (ref "RS-485_OUT3") (pin "5") (pinfunction "5-DC++_5") (pintype "bidirectional"))
    )
    (net (code "138") (name "unconnected-(RS-485_OUT3-7-DC---Pad7)") (class "Default")
      (node (ref "RS-485_OUT3") (pin "7") (pinfunction "7-DC--_7") (pintype "bidirectional"))
    )
    (net (code "139") (name "unconnected-(RS-485_OUT3-8-DC--Pad8)") (class "Default")
      (node (ref "RS-485_OUT3") (pin "8") (pinfunction "8-DC-_8") (pintype "bidirectional"))
    )
    (net (code "140") (name "unconnected-(RS-485_OUT4-4-DC+-Pad4)") (class "Default")
      (node (ref "RS-485_OUT4") (pin "4") (pinfunction "4-DC+_4") (pintype "bidirectional"))
    )
    (net (code "141") (name "unconnected-(RS-485_OUT4-5-DC++-Pad5)") (class "Default")
      (node (ref "RS-485_OUT4") (pin "5") (pinfunction "5-DC++_5") (pintype "bidirectional"))
    )
    (net (code "142") (name "unconnected-(RS-485_OUT4-7-DC---Pad7)") (class "Default")
      (node (ref "RS-485_OUT4") (pin "7") (pinfunction "7-DC--_7") (pintype "bidirectional"))
    )
    (net (code "143") (name "unconnected-(RS-485_OUT4-8-DC--Pad8)") (class "Default")
      (node (ref "RS-485_OUT4") (pin "8") (pinfunction "8-DC-_8") (pintype "bidirectional"))
    )
    (net (code "144") (name "unconnected-(RS-485_OUT5-4-DC+-Pad4)") (class "Default")
      (node (ref "RS-485_OUT5") (pin "4") (pinfunction "4-DC+_4") (pintype "bidirectional"))
    )
    (net (code "145") (name "unconnected-(RS-485_OUT5-5-DC++-Pad5)") (class "Default")
      (node (ref "RS-485_OUT5") (pin "5") (pinfunction "5-DC++_5") (pintype "bidirectional"))
    )
    (net (code "146") (name "unconnected-(RS-485_OUT5-7-DC---Pad7)") (class "Default")
      (node (ref "RS-485_OUT5") (pin "7") (pinfunction "7-DC--_7") (pintype "bidirectional"))
    )
    (net (code "147") (name "unconnected-(RS-485_OUT5-8-DC--Pad8)") (class "Default")
      (node (ref "RS-485_OUT5") (pin "8") (pinfunction "8-DC-_8") (pintype "bidirectional"))
    )
    (net (code "148") (name "unconnected-(RS-485_OUT6-4-DC+-Pad4)") (class "Default")
      (node (ref "RS-485_OUT6") (pin "4") (pinfunction "4-DC+_4") (pintype "bidirectional"))
    )
    (net (code "149") (name "unconnected-(RS-485_OUT6-5-DC++-Pad5)") (class "Default")
      (node (ref "RS-485_OUT6") (pin "5") (pinfunction "5-DC++_5") (pintype "bidirectional"))
    )
    (net (code "150") (name "unconnected-(RS-485_OUT6-7-DC---Pad7)") (class "Default")
      (node (ref "RS-485_OUT6") (pin "7") (pinfunction "7-DC--_7") (pintype "bidirectional"))
    )
    (net (code "151") (name "unconnected-(RS-485_OUT6-8-DC--Pad8)") (class "Default")
      (node (ref "RS-485_OUT6") (pin "8") (pinfunction "8-DC-_8") (pintype "bidirectional"))
    )
    (net (code "152") (name "unconnected-(RS-485_OUT7-4-DC+-Pad4)") (class "Default")
      (node (ref "RS-485_OUT7") (pin "4") (pinfunction "4-DC+_4") (pintype "bidirectional"))
    )
    (net (code "153") (name "unconnected-(RS-485_OUT7-5-DC++-Pad5)") (class "Default")
      (node (ref "RS-485_OUT7") (pin "5") (pinfunction "5-DC++_5") (pintype "bidirectional"))
    )
    (net (code "154") (name "unconnected-(RS-485_OUT7-7-DC---Pad7)") (class "Default")
      (node (ref "RS-485_OUT7") (pin "7") (pinfunction "7-DC--_7") (pintype "bidirectional"))
    )
    (net (code "155") (name "unconnected-(RS-485_OUT7-8-DC--Pad8)") (class "Default")
      (node (ref "RS-485_OUT7") (pin "8") (pinfunction "8-DC-_8") (pintype "bidirectional"))
    )
    (net (code "156") (name "unconnected-(RS-485_OUT8-4-DC+-Pad4)") (class "Default")
      (node (ref "RS-485_OUT8") (pin "4") (pinfunction "4-DC+_4") (pintype "bidirectional"))
    )
    (net (code "157") (name "unconnected-(RS-485_OUT8-5-DC++-Pad5)") (class "Default")
      (node (ref "RS-485_OUT8") (pin "5") (pinfunction "5-DC++_5") (pintype "bidirectional"))
    )
    (net (code "158") (name "unconnected-(RS-485_OUT8-7-DC---Pad7)") (class "Default")
      (node (ref "RS-485_OUT8") (pin "7") (pinfunction "7-DC--_7") (pintype "bidirectional"))
    )
    (net (code "159") (name "unconnected-(RS-485_OUT8-8-DC--Pad8)") (class "Default")
      (node (ref "RS-485_OUT8") (pin "8") (pinfunction "8-DC-_8") (pintype "bidirectional"))
    )
    (net (code "160") (name "unconnected-(RS-485_OUT9-4-DC+-Pad4)") (class "Default")
      (node (ref "RS-485_OUT9") (pin "4") (pinfunction "4-DC+_4") (pintype "bidirectional"))
    )
    (net (code "161") (name "unconnected-(RS-485_OUT9-5-DC++-Pad5)") (class "Default")
      (node (ref "RS-485_OUT9") (pin "5") (pinfunction "5-DC++_5") (pintype "bidirectional"))
    )
    (net (code "162") (name "unconnected-(RS-485_OUT9-7-DC---Pad7)") (class "Default")
      (node (ref "RS-485_OUT9") (pin "7") (pinfunction "7-DC--_7") (pintype "bidirectional"))
    )
    (net (code "163") (name "unconnected-(RS-485_OUT9-8-DC--Pad8)") (class "Default")
      (node (ref "RS-485_OUT9") (pin "8") (pinfunction "8-DC-_8") (pintype "bidirectional"))
    )
    (net (code "164") (name "unconnected-(RS-485_OUT10-4-DC+-Pad4)") (class "Default")
      (node (ref "RS-485_OUT10") (pin "4") (pinfunction "4-DC+_4") (pintype "bidirectional"))
    )
    (net (code "165") (name "unconnected-(RS-485_OUT10-5-DC++-Pad5)") (class "Default")
      (node (ref "RS-485_OUT10") (pin "5") (pinfunction "5-DC++_5") (pintype "bidirectional"))
    )
    (net (code "166") (name "unconnected-(RS-485_OUT10-7-DC---Pad7)") (class "Default")
      (node (ref "RS-485_OUT10") (pin "7") (pinfunction "7-DC--_7") (pintype "bidirectional"))
    )
    (net (code "167") (name "unconnected-(RS-485_OUT10-8-DC--Pad8)") (class "Default")
      (node (ref "RS-485_OUT10") (pin "8") (pinfunction "8-DC-_8") (pintype "bidirectional"))
    )
    (net (code "168") (name "unconnected-(RS-485_OUT11-4-DC+-Pad4)") (class "Default")
      (node (ref "RS-485_OUT11") (pin "4") (pinfunction "4-DC+_4") (pintype "bidirectional"))
    )
    (net (code "169") (name "unconnected-(RS-485_OUT11-5-DC++-Pad5)") (class "Default")
      (node (ref "RS-485_OUT11") (pin "5") (pinfunction "5-DC++_5") (pintype "bidirectional"))
    )
    (net (code "170") (name "unconnected-(RS-485_OUT11-7-DC---Pad7)") (class "Default")
      (node (ref "RS-485_OUT11") (pin "7") (pinfunction "7-DC--_7") (pintype "bidirectional"))
    )
    (net (code "171") (name "unconnected-(RS-485_OUT11-8-DC--Pad8)") (class "Default")
      (node (ref "RS-485_OUT11") (pin "8") (pinfunction "8-DC-_8") (pintype "bidirectional"))
    )
    (net (code "172") (name "unconnected-(RS-485_OUT12-4-DC+-Pad4)") (class "Default")
      (node (ref "RS-485_OUT12") (pin "4") (pinfunction "4-DC+_4") (pintype "bidirectional"))
    )
    (net (code "173") (name "unconnected-(RS-485_OUT12-5-DC++-Pad5)") (class "Default")
      (node (ref "RS-485_OUT12") (pin "5") (pinfunction "5-DC++_5") (pintype "bidirectional"))
    )
    (net (code "174") (name "unconnected-(RS-485_OUT12-7-DC---Pad7)") (class "Default")
      (node (ref "RS-485_OUT12") (pin "7") (pinfunction "7-DC--_7") (pintype "bidirectional"))
    )
    (net (code "175") (name "unconnected-(RS-485_OUT12-8-DC--Pad8)") (class "Default")
      (node (ref "RS-485_OUT12") (pin "8") (pinfunction "8-DC-_8") (pintype "bidirectional"))
    )
    (net (code "176") (name "unconnected-(U$1-Pad49)") (class "Default")
      (node (ref "U$1") (pin "49") (pinfunction "49_49") (pintype "bidirectional"))
    )
    (net (code "177") (name "unconnected-(U$1-Pad50)") (class "Default")
      (node (ref "U$1") (pin "50") (pinfunction "50_50") (pintype "bidirectional"))
    )
    (net (code "178") (name "unconnected-(U$1-Pad51)") (class "Default")
      (node (ref "U$1") (pin "51") (pinfunction "51_51") (pintype "bidirectional"))
    )
    (net (code "179") (name "unconnected-(U$1-Pad52)") (class "Default")
      (node (ref "U$1") (pin "52") (pinfunction "52_52") (pintype "bidirectional"))
    )
    (net (code "180") (name "unconnected-(U$1-Pad53)") (class "Default")
      (node (ref "U$1") (pin "53") (pinfunction "53_53") (pintype "bidirectional"))
    )
    (net (code "181") (name "unconnected-(U$1-Pad54)") (class "Default")
      (node (ref "U$1") (pin "54") (pinfunction "54_54") (pintype "bidirectional"))
    )
    (net (code "182") (name "unconnected-(U$1-Pad55)") (class "Default")
      (node (ref "U$1") (pin "55") (pinfunction "55_55") (pintype "bidirectional"))
    )
    (net (code "183") (name "unconnected-(U$1-Pad56)") (class "Default")
      (node (ref "U$1") (pin "56") (pinfunction "56_56") (pintype "bidirectional"))
    )
    (net (code "184") (name "unconnected-(U$1-Pad57)") (class "Default")
      (node (ref "U$1") (pin "57") (pinfunction "57_57") (pintype "bidirectional"))
    )
    (net (code "185") (name "unconnected-(U$1-Pad58)") (class "Default")
      (node (ref "U$1") (pin "58") (pinfunction "58_58") (pintype "bidirectional"))
    )
    (net (code "186") (name "unconnected-(U$1-Pad59)") (class "Default")
      (node (ref "U$1") (pin "59") (pinfunction "59_59") (pintype "bidirectional"))
    )
    (net (code "187") (name "unconnected-(U$1-Pad60)") (class "Default")
      (node (ref "U$1") (pin "60") (pinfunction "60_60") (pintype "bidirectional"))
    )
    (net (code "188") (name "unconnected-(U$1-Pad61)") (class "Default")
      (node (ref "U$1") (pin "61") (pinfunction "61_61") (pintype "bidirectional"))
    )
    (net (code "189") (name "unconnected-(U$1-Pad62)") (class "Default")
      (node (ref "U$1") (pin "62") (pinfunction "62_62") (pintype "bidirectional"))
    )
    (net (code "190") (name "unconnected-(U$1-Pad63)") (class "Default")
      (node (ref "U$1") (pin "63") (pinfunction "63_63") (pintype "bidirectional"))
    )
    (net (code "191") (name "unconnected-(U$1-Pad64)") (class "Default")
      (node (ref "U$1") (pin "64") (pinfunction "64_64") (pintype "bidirectional"))
    )
    (net (code "192") (name "unconnected-(U$1-Pad65)") (class "Default")
      (node (ref "U$1") (pin "65") (pinfunction "65_65") (pintype "bidirectional"))
    )
    (net (code "193") (name "unconnected-(U$1-Pad66)") (class "Default")
      (node (ref "U$1") (pin "66") (pinfunction "66_66") (pintype "bidirectional"))
    )
    (net (code "194") (name "unconnected-(U$1-Pad67)") (class "Default")
      (node (ref "U$1") (pin "67") (pinfunction "67_67") (pintype "bidirectional"))
    )
    (net (code "195") (name "unconnected-(U$1-Pad68)") (class "Default")
      (node (ref "U$1") (pin "68") (pinfunction "68_68") (pintype "bidirectional"))
    )
  )
)
